# ethernet.net
KiCad netlist of a schematic drawn in Altium Designer
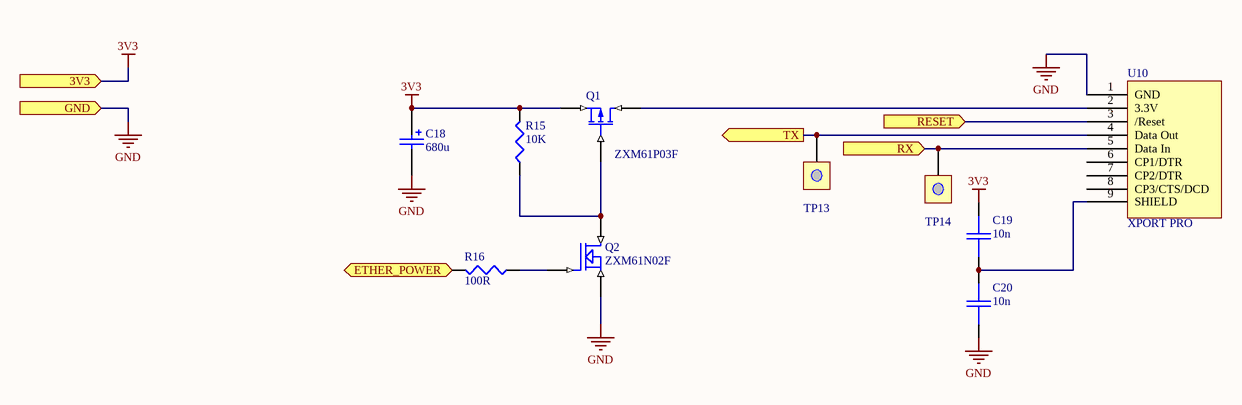
[diagram p0: ethernet.SchDoc]

(export (version "E")
  (design (tool "Eeschema 10.0.6"))
  (components
    (comp (ref "C18")
      (value "680u")
      (footprint "MCCT-CASED")
      (description "Polarized Capacitor (Surface Mount)")
      (fields (field (name "MANUFACTURER") "Generic Components") (field (name "PUBLISHER") "Altium Limited"))
      (libsource (lib "RCLDQ") (part "CAP POL3"))
    )
    (comp (ref "C19")
      (value "10n")
      (footprint "0805")
      (description "Capacitor")
      (libsource (lib "RCLDQ") (part "CAP"))
    )
    (comp (ref "C20")
      (value "10n")
      (footprint "0805")
      (description "Capacitor")
      (libsource (lib "RCLDQ") (part "CAP"))
    )
    (comp (ref "Q1")
      (value "ZXM61P03F")
      (footprint "SOT23-3")
      (description "1.1A, 30V P-Channel Enhancement mode FET")
      (libsource (lib "RCLDQ") (part "ZXM61P03F"))
    )
    (comp (ref "Q2")
      (value "ZXM61N02F")
      (footprint "SOT23-3")
      (description "1.7A, 20V N-Channel Enhancement mode FET")
      (libsource (lib "RCLDQ") (part "ZXM61N02F"))
    )
    (comp (ref "R15")
      (value "10K")
      (footprint "0603")
      (description "Resistor")
      (libsource (lib "RCLDQ") (part "RES1"))
    )
    (comp (ref "R16")
      (value "100R")
      (footprint "0603")
      (description "Resistor")
      (libsource (lib "RCLDQ") (part "RES1"))
    )
    (comp (ref "TP13")
      (value "TEST")
      (footprint "TESTPOINT")
      (description "TEST POINT")
      (libsource (lib "Miscellaneous") (part "TEST"))
    )
    (comp (ref "TP14")
      (value "TEST")
      (footprint "TESTPOINT")
      (description "TEST POINT")
      (libsource (lib "Miscellaneous") (part "TEST"))
    )
    (comp (ref "U10")
      (value "XPORT PRO")
      (footprint "XPORT PRO")
      (description "Lantronix Xport Pro")
      (libsource (lib "sion") (part "Xport Pro"))
    )
  )
  (nets
    (net (code "1") (name "/ETHER_POWER") (class "Default")
      (node (ref "R16") (pin "2") (pinfunction "2_2") (pintype "passive"))
    )
    (net (code "2") (name "/RESET") (class "Default")
      (node (ref "U10") (pin "3") (pinfunction "/Reset_3") (pintype "passive"))
    )
    (net (code "3") (name "/RX") (class "Default")
      (node (ref "TP14") (pin "0") (pinfunction "TP_0") (pintype "passive"))
      (node (ref "U10") (pin "5") (pinfunction "Data_In_5") (pintype "passive"))
    )
    (net (code "4") (name "/TX") (class "Default")
      (node (ref "TP13") (pin "0") (pinfunction "TP_0") (pintype "passive"))
      (node (ref "U10") (pin "4") (pinfunction "Data_Out_4") (pintype "passive"))
    )
    (net (code "5") (name "3V3") (class "Default")
      (node (ref "C18") (pin "1") (pinfunction "1_1") (pintype "passive"))
      (node (ref "C19") (pin "1") (pinfunction "1_1") (pintype "passive"))
      (node (ref "Q1") (pin "3") (pinfunction "D_3") (pintype "input"))
      (node (ref "R15") (pin "2") (pinfunction "2_2") (pintype "passive"))
    )
    (net (code "6") (name "GND") (class "Default")
      (node (ref "C18") (pin "2") (pinfunction "2_2") (pintype "passive"))
      (node (ref "C20") (pin "2") (pinfunction "2_2") (pintype "passive"))
      (node (ref "Q2") (pin "2") (pinfunction "S_2") (pintype "input"))
      (node (ref "U10") (pin "1") (pinfunction "GND_1") (pintype "passive"))
    )
    (net (code "7") (name "Net-(Q1-G)") (class "Default")
      (node (ref "Q1") (pin "1") (pinfunction "G_1") (pintype "input"))
      (node (ref "Q2") (pin "3") (pinfunction "D_3") (pintype "input"))
      (node (ref "R15") (pin "1") (pinfunction "1_1") (pintype "passive"))
    )
    (net (code "8") (name "Net-(Q1-S)") (class "Default")
      (node (ref "Q1") (pin "2") (pinfunction "S_2") (pintype "input"))
      (node (ref "U10") (pin "2") (pinfunction "3.3V_2") (pintype "passive"))
    )
    (net (code "9") (name "Net-(Q2-G)") (class "Default")
      (node (ref "Q2") (pin "1") (pinfunction "G_1") (pintype "input"))
      (node (ref "R16") (pin "1") (pinfunction "1_1") (pintype "passive"))
    )
    (net (code "10") (name "Net-(U10-SHIELD)") (class "Default")
      (node (ref "C19") (pin "2") (pinfunction "2_2") (pintype "passive"))
      (node (ref "C20") (pin "1") (pinfunction "1_1") (pintype "passive"))
      (node (ref "U10") (pin "9") (pinfunction "SHIELD_9") (pintype "passive"))
    )
    (net (code "11") (name "unconnected-(U10-CP1{slash}DTR-Pad6)") (class "Default")
      (node (ref "U10") (pin "6") (pinfunction "CP1/DTR_6") (pintype "passive"))
    )
    (net (code "12") (name "unconnected-(U10-CP2{slash}DTR-Pad7)") (class "Default")
      (node (ref "U10") (pin "7") (pinfunction "CP2/DTR_7") (pintype "passive"))
    )
    (net (code "13") (name "unconnected-(U10-CP3{slash}CTS{slash}DCD-Pad8)") (class "Default")
      (node (ref "U10") (pin "8") (pinfunction "CP3/CTS/DCD_8") (pintype "passive"))
    )
  )
)
